# GardenJarLight_V1.net
KiCad netlist of a schematic drawn in EAGLE
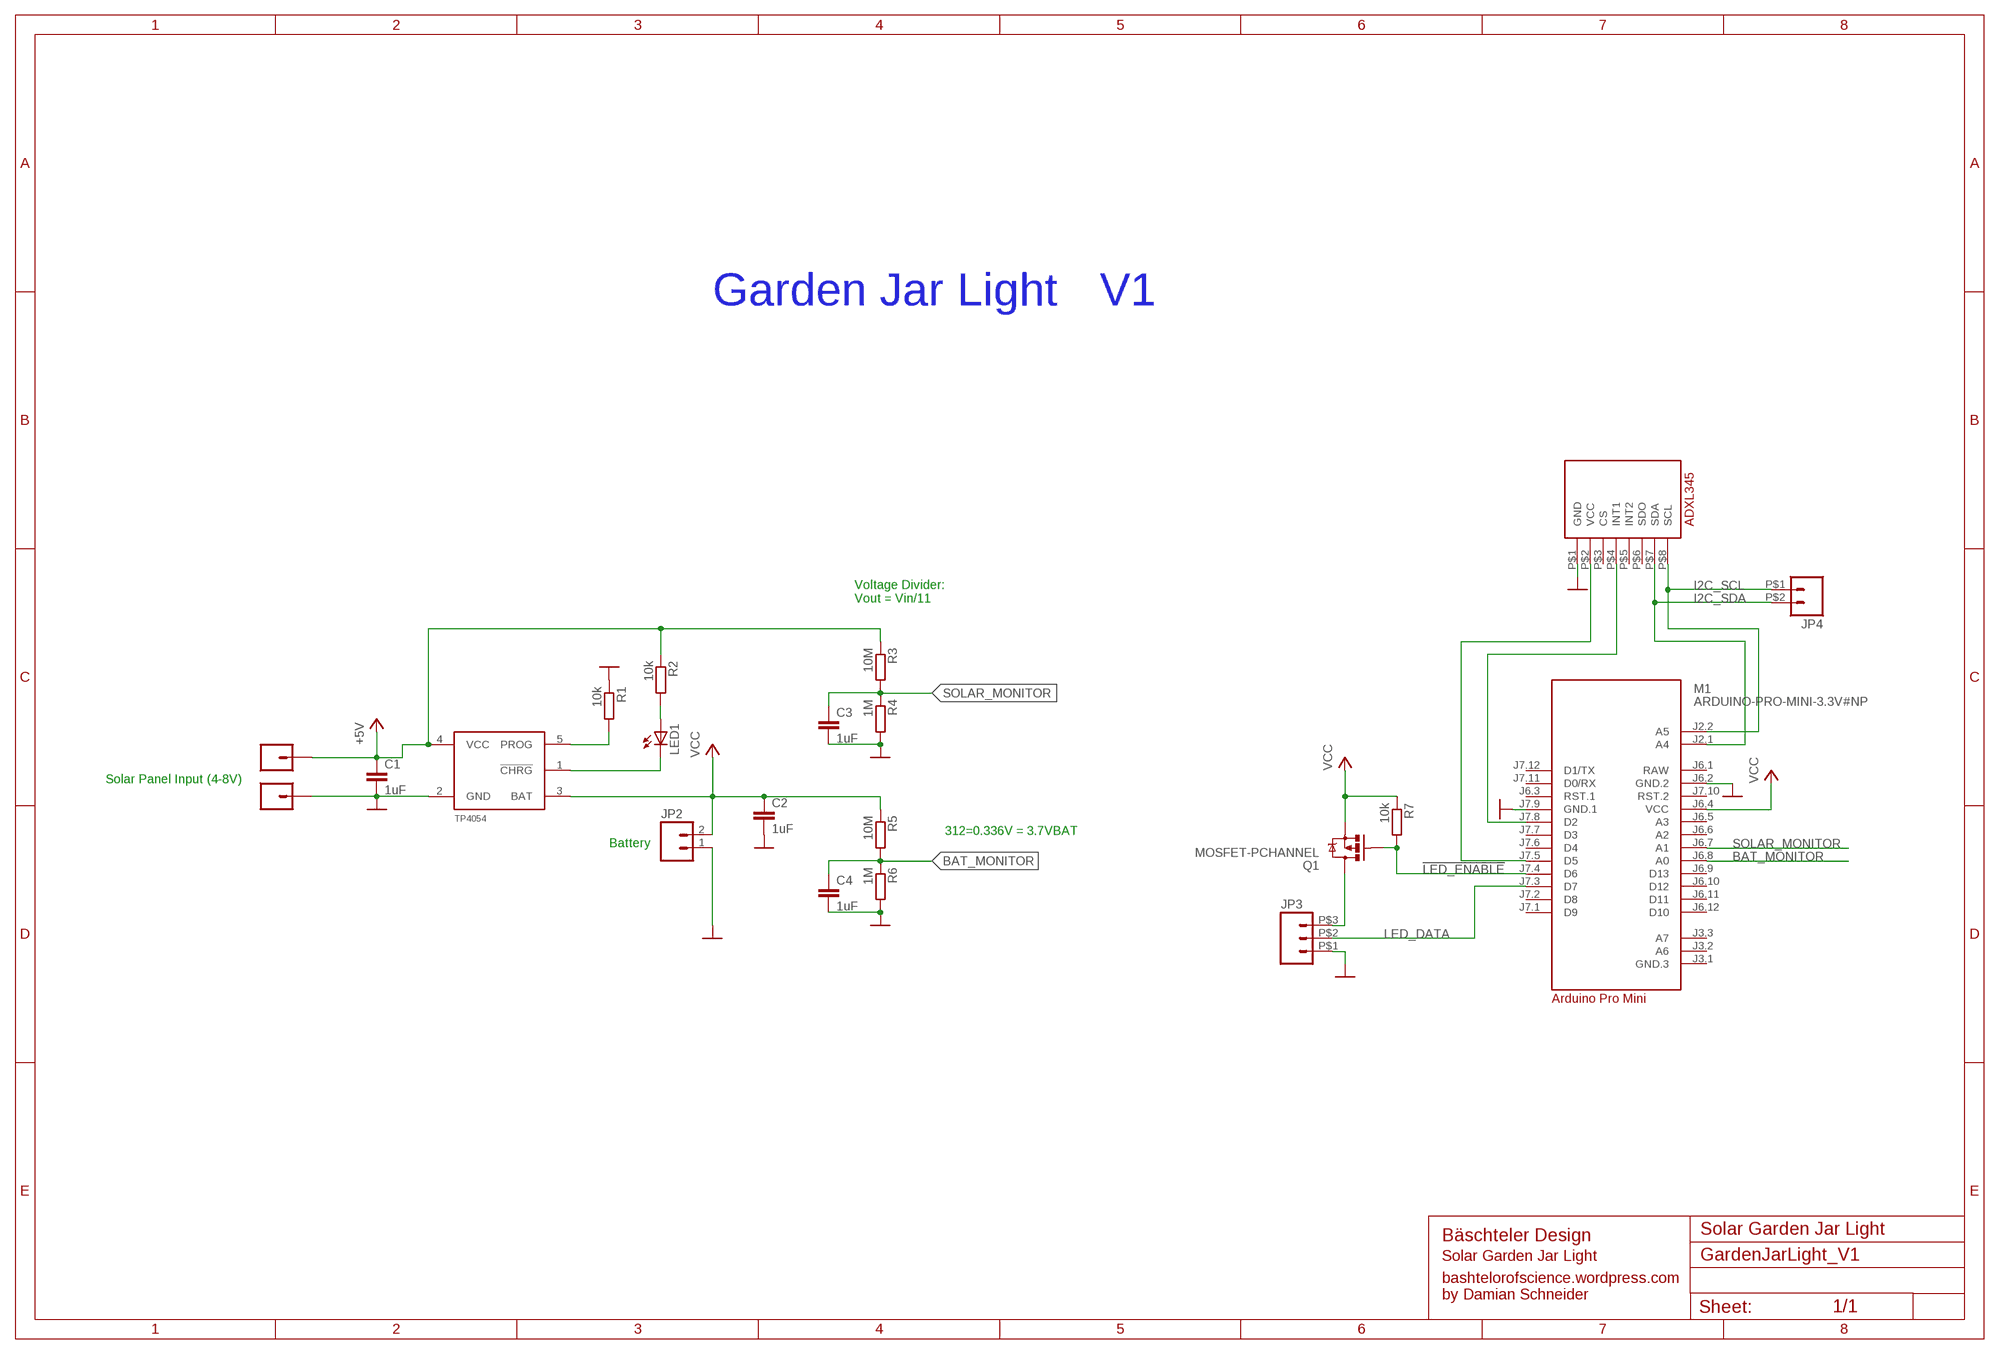
[diagram p0: schematic, sheet 1]

(export (version "E")
  (design (tool "Eeschema 10.0.6"))
  (components
    (comp (ref "C1")
      (value "1uF")
      (footprint "eagle-import:C0805")
      (libsource (lib "eagle-import") (part "C-EUC0805"))
    )
    (comp (ref "C2")
      (value "1uF")
      (footprint "eagle-import:C0805")
      (libsource (lib "eagle-import") (part "C-EUC0805"))
    )
    (comp (ref "C3")
      (value "1uF")
      (footprint "eagle-import:C0805")
      (libsource (lib "eagle-import") (part "C-EUC0805"))
    )
    (comp (ref "C4")
      (value "1uF")
      (footprint "eagle-import:C0805")
      (libsource (lib "eagle-import") (part "C-EUC0805"))
    )
    (comp (ref "IC1")
      (value "TP4054_LIPO_CHARGER")
      (footprint "eagle-import:SOT23-5")
      (libsource (lib "eagle-import") (part "TP4054_LIPO_CHARGER"))
    )
    (comp (ref "JP1")
      (value "M01PTH")
      (footprint "eagle-import:1X01")
      (libsource (lib "eagle-import") (part "M01PTH"))
    )
    (comp (ref "JP2")
      (value "M021X02_NO_SILK")
      (footprint "eagle-import:1X02_NO_SILK")
      (libsource (lib "eagle-import") (part "M021X02_NO_SILK"))
    )
    (comp (ref "JP3")
      (value "M03SMD_LONG")
      (footprint "eagle-import:SMD_HEADER_3P_LONG")
      (libsource (lib "eagle-import") (part "M03SMD_LONG"))
    )
    (comp (ref "JP4")
      (value "M02")
      (footprint "eagle-import:SMD_HEADER_2P")
      (libsource (lib "eagle-import") (part "M02"))
    )
    (comp (ref "JP5")
      (value "M01PTH")
      (footprint "eagle-import:1X01")
      (libsource (lib "eagle-import") (part "M01PTH"))
    )
    (comp (ref "LED1")
      (value "LEDCHIPLED_0805")
      (footprint "eagle-import:CHIPLED_0805")
      (libsource (lib "eagle-import") (part "LEDCHIPLED_0805"))
    )
    (comp (ref "M1")
      (value "ARDUINO-PRO-MINI-3.3V#NP")
      (footprint "eagle-import:ARDUINO-PRO-MINI#NP")
      (libsource (lib "eagle-import") (part "ARDUINO-PRO-MINI-#NP3.3V"))
    )
    (comp (ref "Q1")
      (value "MOSFET-PCHANNEL")
      (footprint "eagle-import:SOT23-3")
      (libsource (lib "eagle-import") (part "MOSFET-PCHANNEL"))
    )
    (comp (ref "R1")
      (value "10k")
      (footprint "eagle-import:R0805")
      (libsource (lib "eagle-import") (part "R-EU_R0805"))
    )
    (comp (ref "R2")
      (value "10k")
      (footprint "eagle-import:R0805")
      (libsource (lib "eagle-import") (part "R-EU_R0805"))
    )
    (comp (ref "R3")
      (value "10M")
      (footprint "eagle-import:R0805")
      (libsource (lib "eagle-import") (part "R-EU_R0805"))
    )
    (comp (ref "R4")
      (value "1M")
      (footprint "eagle-import:R0805")
      (libsource (lib "eagle-import") (part "R-EU_R0805"))
    )
    (comp (ref "R5")
      (value "10M")
      (footprint "eagle-import:R0805")
      (libsource (lib "eagle-import") (part "R-EU_R0805"))
    )
    (comp (ref "R6")
      (value "1M")
      (footprint "eagle-import:R0805")
      (libsource (lib "eagle-import") (part "R-EU_R0805"))
    )
    (comp (ref "R7")
      (value "10k")
      (footprint "eagle-import:R0805")
      (libsource (lib "eagle-import") (part "R-EU_R0805"))
    )
    (comp (ref "U$1")
      (value "ADXL345")
      (footprint "eagle-import:ADXL345")
      (libsource (lib "eagle-import") (part "ADXL345"))
    )
  )
  (nets
    (net (code "1") (name "+5V") (class "Default")
      (node (ref "C1") (pin "1") (pinfunction "1_1") (pintype "passive"))
      (node (ref "IC1") (pin "4") (pinfunction "VCC_4") (pintype "bidirectional"))
      (node (ref "JP1") (pin "1") (pinfunction "1_1") (pintype "passive"))
      (node (ref "R2") (pin "1") (pinfunction "1_1") (pintype "passive"))
      (node (ref "R3") (pin "1") (pinfunction "1_1") (pintype "passive"))
    )
    (net (code "2") (name "/I2C_SCL") (class "Default")
      (node (ref "JP4") (pin "P$1") (pinfunction "1_P$1") (pintype "passive"))
      (node (ref "M1") (pin "J2.2") (pinfunction "A5_J2.2") (pintype "bidirectional"))
      (node (ref "U$1") (pin "P$8") (pinfunction "SCL_P$8") (pintype "bidirectional"))
    )
    (net (code "3") (name "/I2C_SDA") (class "Default")
      (node (ref "JP4") (pin "P$2") (pinfunction "2_P$2") (pintype "passive"))
      (node (ref "M1") (pin "J2.1") (pinfunction "A4_J2.1") (pintype "bidirectional"))
      (node (ref "U$1") (pin "P$7") (pinfunction "SDA_P$7") (pintype "bidirectional"))
    )
    (net (code "4") (name "/LED_DATA") (class "Default")
      (node (ref "JP3") (pin "P$2") (pinfunction "2_P$2") (pintype "passive"))
      (node (ref "M1") (pin "J7.3") (pinfunction "D7_J7.3") (pintype "bidirectional"))
    )
    (net (code "5") (name "/RAW") (class "Default")
      (node (ref "M1") (pin "J6.1") (pinfunction "RAW_J6.1") (pintype "power_in"))
    )
    (net (code "6") (name "/~{LED_ENABLE}") (class "Default")
      (node (ref "M1") (pin "J7.4") (pinfunction "D6_J7.4") (pintype "bidirectional"))
      (node (ref "Q1") (pin "1") (pinfunction "G_1") (pintype "passive"))
      (node (ref "R7") (pin "2") (pinfunction "2_2") (pintype "passive"))
    )
    (net (code "7") (name "BAT_MONITOR") (class "Default")
      (node (ref "C4") (pin "1") (pinfunction "1_1") (pintype "passive"))
      (node (ref "M1") (pin "J6.8") (pinfunction "A0_J6.8") (pintype "bidirectional"))
      (node (ref "R5") (pin "2") (pinfunction "2_2") (pintype "passive"))
      (node (ref "R6") (pin "1") (pinfunction "1_1") (pintype "passive"))
    )
    (net (code "8") (name "GND") (class "Default")
      (node (ref "C1") (pin "2") (pinfunction "2_2") (pintype "passive"))
      (node (ref "C2") (pin "2") (pinfunction "2_2") (pintype "passive"))
      (node (ref "C3") (pin "2") (pinfunction "2_2") (pintype "passive"))
      (node (ref "C4") (pin "2") (pinfunction "2_2") (pintype "passive"))
      (node (ref "IC1") (pin "2") (pinfunction "GND_2") (pintype "bidirectional"))
      (node (ref "JP2") (pin "1") (pinfunction "1_1") (pintype "passive"))
      (node (ref "JP3") (pin "P$1") (pinfunction "1_P$1") (pintype "passive"))
      (node (ref "JP5") (pin "1") (pinfunction "1_1") (pintype "passive"))
      (node (ref "M1") (pin "J6.2") (pinfunction "GND.2_J6.2") (pintype "power_in"))
      (node (ref "M1") (pin "J7.9") (pinfunction "GND.1_J7.9") (pintype "power_in"))
      (node (ref "R1") (pin "1") (pinfunction "1_1") (pintype "passive"))
      (node (ref "R4") (pin "2") (pinfunction "2_2") (pintype "passive"))
      (node (ref "R6") (pin "2") (pinfunction "2_2") (pintype "passive"))
      (node (ref "U$1") (pin "P$1") (pinfunction "GND_P$1") (pintype "bidirectional"))
    )
    (net (code "9") (name "Net-(IC1-PROG)") (class "Default")
      (node (ref "IC1") (pin "5") (pinfunction "PROG_5") (pintype "bidirectional"))
      (node (ref "R1") (pin "2") (pinfunction "2_2") (pintype "passive"))
    )
    (net (code "10") (name "Net-(IC1-~{CHRG})") (class "Default")
      (node (ref "IC1") (pin "1") (pinfunction "~{CHRG}_1") (pintype "bidirectional"))
      (node (ref "LED1") (pin "C") (pinfunction "C_C") (pintype "passive"))
    )
    (net (code "11") (name "Net-(JP3-3)") (class "Default")
      (node (ref "JP3") (pin "P$3") (pinfunction "3_P$3") (pintype "passive"))
      (node (ref "Q1") (pin "3") (pinfunction "D_3") (pintype "passive"))
    )
    (net (code "12") (name "Net-(LED1-PadA)") (class "Default")
      (node (ref "LED1") (pin "A") (pinfunction "A_A") (pintype "passive"))
      (node (ref "R2") (pin "2") (pinfunction "2_2") (pintype "passive"))
    )
    (net (code "13") (name "Net-(M1-D2)") (class "Default")
      (node (ref "M1") (pin "J7.8") (pinfunction "D2_J7.8") (pintype "bidirectional"))
      (node (ref "U$1") (pin "P$4") (pinfunction "INT1_P$4") (pintype "bidirectional"))
    )
    (net (code "14") (name "Net-(M1-D5)") (class "Default")
      (node (ref "M1") (pin "J7.5") (pinfunction "D5_J7.5") (pintype "bidirectional"))
      (node (ref "U$1") (pin "P$2") (pinfunction "VCC_P$2") (pintype "bidirectional"))
    )
    (net (code "15") (name "SOLAR_MONITOR") (class "Default")
      (node (ref "C3") (pin "1") (pinfunction "1_1") (pintype "passive"))
      (node (ref "M1") (pin "J6.7") (pinfunction "A1_J6.7") (pintype "bidirectional"))
      (node (ref "R3") (pin "2") (pinfunction "2_2") (pintype "passive"))
      (node (ref "R4") (pin "1") (pinfunction "1_1") (pintype "passive"))
    )
    (net (code "16") (name "VCC") (class "Default")
      (node (ref "C2") (pin "1") (pinfunction "1_1") (pintype "passive"))
      (node (ref "IC1") (pin "3") (pinfunction "BAT_3") (pintype "bidirectional"))
      (node (ref "JP2") (pin "2") (pinfunction "2_2") (pintype "passive"))
      (node (ref "M1") (pin "J6.4") (pinfunction "VCC_J6.4") (pintype "power_in"))
      (node (ref "Q1") (pin "2") (pinfunction "S_2") (pintype "passive"))
      (node (ref "R5") (pin "1") (pinfunction "1_1") (pintype "passive"))
      (node (ref "R7") (pin "1") (pinfunction "1_1") (pintype "passive"))
    )
    (net (code "17") (name "unconnected-(M1-A2-PadJ6.6)") (class "Default")
      (node (ref "M1") (pin "J6.6") (pinfunction "A2_J6.6") (pintype "bidirectional"))
    )
    (net (code "18") (name "unconnected-(M1-A3-PadJ6.5)") (class "Default")
      (node (ref "M1") (pin "J6.5") (pinfunction "A3_J6.5") (pintype "bidirectional"))
    )
    (net (code "19") (name "unconnected-(M1-A6-PadJ3.2)") (class "Default")
      (node (ref "M1") (pin "J3.2") (pinfunction "A6_J3.2") (pintype "bidirectional"))
    )
    (net (code "20") (name "unconnected-(M1-A7-PadJ3.3)") (class "Default")
      (node (ref "M1") (pin "J3.3") (pinfunction "A7_J3.3") (pintype "bidirectional"))
    )
    (net (code "21") (name "unconnected-(M1-D0{slash}RX-PadJ7.11)") (class "Default")
      (node (ref "M1") (pin "J7.11") (pinfunction "D0/RX_J7.11") (pintype "bidirectional"))
    )
    (net (code "22") (name "unconnected-(M1-D1{slash}TX-PadJ7.12)") (class "Default")
      (node (ref "M1") (pin "J7.12") (pinfunction "D1/TX_J7.12") (pintype "bidirectional"))
    )
    (net (code "23") (name "unconnected-(M1-D3-PadJ7.7)") (class "Default")
      (node (ref "M1") (pin "J7.7") (pinfunction "D3_J7.7") (pintype "bidirectional"))
    )
    (net (code "24") (name "unconnected-(M1-D4-PadJ7.6)") (class "Default")
      (node (ref "M1") (pin "J7.6") (pinfunction "D4_J7.6") (pintype "bidirectional"))
    )
    (net (code "25") (name "unconnected-(M1-D8-PadJ7.2)") (class "Default")
      (node (ref "M1") (pin "J7.2") (pinfunction "D8_J7.2") (pintype "bidirectional"))
    )
    (net (code "26") (name "unconnected-(M1-D9-PadJ7.1)") (class "Default")
      (node (ref "M1") (pin "J7.1") (pinfunction "D9_J7.1") (pintype "bidirectional"))
    )
    (net (code "27") (name "unconnected-(M1-D10-PadJ6.12)") (class "Default")
      (node (ref "M1") (pin "J6.12") (pinfunction "D10_J6.12") (pintype "bidirectional"))
    )
    (net (code "28") (name "unconnected-(M1-D11-PadJ6.11)") (class "Default")
      (node (ref "M1") (pin "J6.11") (pinfunction "D11_J6.11") (pintype "bidirectional"))
    )
    (net (code "29") (name "unconnected-(M1-D12-PadJ6.10)") (class "Default")
      (node (ref "M1") (pin "J6.10") (pinfunction "D12_J6.10") (pintype "bidirectional"))
    )
    (net (code "30") (name "unconnected-(M1-D13-PadJ6.9)") (class "Default")
      (node (ref "M1") (pin "J6.9") (pinfunction "D13_J6.9") (pintype "bidirectional"))
    )
    (net (code "31") (name "unconnected-(M1-GND.3-PadJ3.1)") (class "Default")
      (node (ref "M1") (pin "J3.1") (pinfunction "GND.3_J3.1") (pintype "bidirectional"))
    )
    (net (code "32") (name "unconnected-(M1-RST.1-PadJ6.3)") (class "Default")
      (node (ref "M1") (pin "J6.3") (pinfunction "RST.1_J6.3") (pintype "bidirectional"))
    )
    (net (code "33") (name "unconnected-(M1-RST.2-PadJ7.10)") (class "Default")
      (node (ref "M1") (pin "J7.10") (pinfunction "RST.2_J7.10") (pintype "bidirectional"))
    )
    (net (code "34") (name "unconnected-(U$1-CS-PadP$3)") (class "Default")
      (node (ref "U$1") (pin "P$3") (pinfunction "CS_P$3") (pintype "bidirectional"))
    )
    (net (code "35") (name "unconnected-(U$1-INT2-PadP$5)") (class "Default")
      (node (ref "U$1") (pin "P$5") (pinfunction "INT2_P$5") (pintype "bidirectional"))
    )
    (net (code "36") (name "unconnected-(U$1-SDO-PadP$6)") (class "Default")
      (node (ref "U$1") (pin "P$6") (pinfunction "SDO_P$6") (pintype "bidirectional"))
    )
  )
)
